# RC_shieldV2.net
KiCad netlist of a schematic drawn in EAGLE
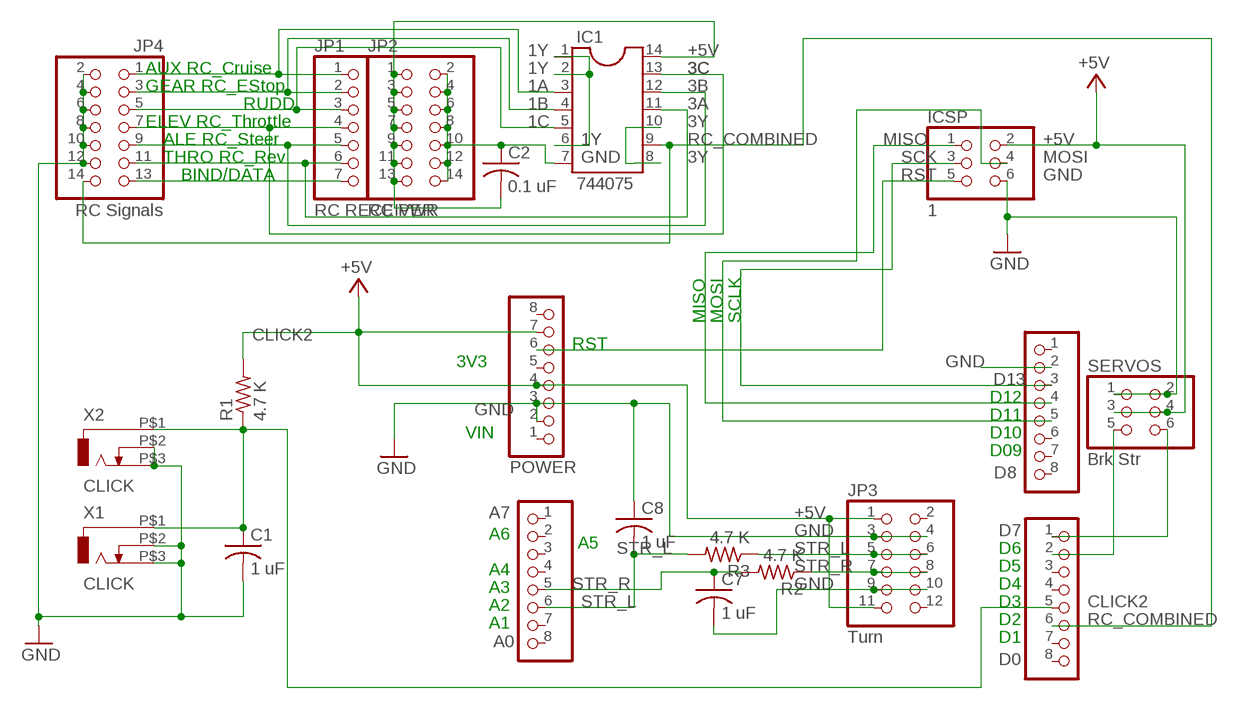
[diagram p0: schematic, sheet 1]

(export (version "E")
  (design (tool "Eeschema 10.0.6"))
  (components
    (comp (ref "A0")
      (value "A7")
      (footprint "eagle-import:1X08")
      (libsource (lib "eagle-import") (part "PINHD-1X8"))
    )
    (comp (ref "C1")
      (value "1 uF")
      (footprint "eagle-import:C025-030X050")
      (libsource (lib "eagle-import") (part "C-US025-030X050"))
    )
    (comp (ref "C2")
      (value "0.1 uF")
      (footprint "eagle-import:C025-030X050")
      (libsource (lib "eagle-import") (part "C-US025-030X050"))
    )
    (comp (ref "C7")
      (value "1 uF")
      (footprint "eagle-import:C025-030X050")
      (libsource (lib "eagle-import") (part "C-US025-030X050"))
    )
    (comp (ref "C8")
      (value "1 uF")
      (footprint "eagle-import:C025-030X050")
      (libsource (lib "eagle-import") (part "C-US025-030X050"))
    )
    (comp (ref "D0")
      (value "D7")
      (footprint "eagle-import:1X08")
      (libsource (lib "eagle-import") (part "PINHD-1X8"))
    )
    (comp (ref "D8")
      (value "D13")
      (footprint "eagle-import:1X08")
      (libsource (lib "eagle-import") (part "PINHD-1X8"))
    )
    (comp (ref "IC1")
      (value "744075")
      (footprint "eagle-import:DIL14")
      (libsource (lib "eagle-import") (part "DIL14"))
    )
    (comp (ref "ICSP")
      (value "1")
      (footprint "eagle-import:2X03")
      (libsource (lib "eagle-import") (part "PINHD-2X3"))
    )
    (comp (ref "JP1")
      (value "RC RECEIVER")
      (footprint "eagle-import:1X07")
      (libsource (lib "eagle-import") (part "PINHD-1X7"))
    )
    (comp (ref "JP2")
      (value "RC PWR")
      (footprint "eagle-import:2X07")
      (libsource (lib "eagle-import") (part "PINHD-2X7"))
    )
    (comp (ref "JP3")
      (value "Turn")
      (footprint "eagle-import:2X06")
      (libsource (lib "eagle-import") (part "PINHD-2X6"))
    )
    (comp (ref "JP4")
      (value "RC Signals")
      (footprint "eagle-import:2X07")
      (libsource (lib "eagle-import") (part "PINHD-2X7"))
    )
    (comp (ref "POWER")
      (value "GND")
      (footprint "eagle-import:1X08")
      (libsource (lib "eagle-import") (part "PINHD-1X8"))
    )
    (comp (ref "R1")
      (value "4.7 K")
      (footprint "eagle-import:0207_10")
      (libsource (lib "eagle-import") (part "R-US_0207/10"))
    )
    (comp (ref "R2")
      (value "4.7 K")
      (footprint "eagle-import:0207_10")
      (libsource (lib "eagle-import") (part "R-US_0207/10"))
    )
    (comp (ref "R3")
      (value "4.7 K")
      (footprint "eagle-import:0207_10")
      (libsource (lib "eagle-import") (part "R-US_0207/10"))
    )
    (comp (ref "SERVOS")
      (value "Brk Str")
      (footprint "eagle-import:2X03")
      (libsource (lib "eagle-import") (part "PINHD-2X3"))
    )
    (comp (ref "X1")
      (value "CLICK")
      (footprint "eagle-import:ODO_JACK")
      (libsource (lib "eagle-import") (part "ODO_JACK"))
    )
    (comp (ref "X2")
      (value "CLICK")
      (footprint "eagle-import:ODO_JACK")
      (libsource (lib "eagle-import") (part "ODO_JACK"))
    )
  )
  (nets
    (net (code "1") (name "+5V") (class "Default")
      (node (ref "C2") (pin "2") (pinfunction "2_2") (pintype "passive"))
      (node (ref "IC1") (pin "14") (pinfunction "14_14") (pintype "passive"))
      (node (ref "ICSP") (pin "2") (pinfunction "2_2") (pintype "passive"))
      (node (ref "JP2") (pin "1") (pinfunction "1_1") (pintype "passive"))
      (node (ref "JP2") (pin "11") (pinfunction "11_11") (pintype "passive"))
      (node (ref "JP2") (pin "13") (pinfunction "13_13") (pintype "passive"))
      (node (ref "JP2") (pin "3") (pinfunction "3_3") (pintype "passive"))
      (node (ref "JP2") (pin "5") (pinfunction "5_5") (pintype "passive"))
      (node (ref "JP2") (pin "7") (pinfunction "7_7") (pintype "passive"))
      (node (ref "JP2") (pin "9") (pinfunction "9_9") (pintype "passive"))
      (node (ref "JP3") (pin "1") (pinfunction "1_1") (pintype "passive"))
      (node (ref "JP3") (pin "11") (pinfunction "11_11") (pintype "passive"))
      (node (ref "POWER") (pin "4") (pinfunction "4_4") (pintype "passive"))
      (node (ref "POWER") (pin "7") (pinfunction "7_7") (pintype "passive"))
      (node (ref "R1") (pin "2") (pinfunction "2_2") (pintype "passive"))
      (node (ref "SERVOS") (pin "3") (pinfunction "3_3") (pintype "passive"))
      (node (ref "SERVOS") (pin "4") (pinfunction "4_4") (pintype "passive"))
    )
    (net (code "2") (name "/1A") (class "Default")
      (node (ref "IC1") (pin "3") (pinfunction "3_3") (pintype "passive"))
      (node (ref "JP1") (pin "1") (pinfunction "1_1") (pintype "passive"))
      (node (ref "JP4") (pin "1") (pinfunction "1_1") (pintype "passive"))
    )
    (net (code "3") (name "/1B") (class "Default")
      (node (ref "IC1") (pin "4") (pinfunction "4_4") (pintype "passive"))
      (node (ref "JP1") (pin "2") (pinfunction "2_2") (pintype "passive"))
      (node (ref "JP4") (pin "3") (pinfunction "3_3") (pintype "passive"))
    )
    (net (code "4") (name "/1C") (class "Default")
      (node (ref "IC1") (pin "5") (pinfunction "5_5") (pintype "passive"))
      (node (ref "JP1") (pin "3") (pinfunction "3_3") (pintype "passive"))
      (node (ref "JP4") (pin "5") (pinfunction "5_5") (pintype "passive"))
    )
    (net (code "5") (name "/1Y") (class "Default")
      (node (ref "IC1") (pin "1") (pinfunction "1_1") (pintype "passive"))
      (node (ref "IC1") (pin "2") (pinfunction "2_2") (pintype "passive"))
      (node (ref "IC1") (pin "6") (pinfunction "6_6") (pintype "passive"))
    )
    (net (code "6") (name "/3A") (class "Default")
      (node (ref "IC1") (pin "11") (pinfunction "11_11") (pintype "passive"))
      (node (ref "JP1") (pin "6") (pinfunction "6_6") (pintype "passive"))
      (node (ref "JP4") (pin "11") (pinfunction "11_11") (pintype "passive"))
    )
    (net (code "7") (name "/3B") (class "Default")
      (node (ref "IC1") (pin "12") (pinfunction "12_12") (pintype "passive"))
      (node (ref "JP1") (pin "5") (pinfunction "5_5") (pintype "passive"))
      (node (ref "JP4") (pin "9") (pinfunction "9_9") (pintype "passive"))
    )
    (net (code "8") (name "/3C") (class "Default")
      (node (ref "IC1") (pin "13") (pinfunction "13_13") (pintype "passive"))
      (node (ref "JP1") (pin "4") (pinfunction "4_4") (pintype "passive"))
      (node (ref "JP4") (pin "7") (pinfunction "7_7") (pintype "passive"))
    )
    (net (code "9") (name "/3Y") (class "Default")
      (node (ref "IC1") (pin "10") (pinfunction "10_10") (pintype "passive"))
      (node (ref "IC1") (pin "8") (pinfunction "8_8") (pintype "passive"))
    )
    (net (code "10") (name "/CLICK2") (class "Default")
      (node (ref "C1") (pin "1") (pinfunction "1_1") (pintype "passive"))
      (node (ref "D0") (pin "5") (pinfunction "5_5") (pintype "passive"))
      (node (ref "R1") (pin "1") (pinfunction "1_1") (pintype "passive"))
      (node (ref "X1") (pin "P$1") (pinfunction "1_P$1") (pintype "passive"))
      (node (ref "X2") (pin "P$1") (pinfunction "1_P$1") (pintype "passive"))
    )
    (net (code "11") (name "/MISO") (class "Default")
      (node (ref "D8") (pin "4") (pinfunction "4_4") (pintype "passive"))
      (node (ref "ICSP") (pin "1") (pinfunction "1_1") (pintype "passive"))
    )
    (net (code "12") (name "/MOSI") (class "Default")
      (node (ref "D8") (pin "5") (pinfunction "5_5") (pintype "passive"))
      (node (ref "ICSP") (pin "4") (pinfunction "4_4") (pintype "passive"))
    )
    (net (code "13") (name "/RC_COMBINED") (class "Default")
      (node (ref "D0") (pin "6") (pinfunction "6_6") (pintype "passive"))
      (node (ref "IC1") (pin "9") (pinfunction "9_9") (pintype "passive"))
      (node (ref "JP4") (pin "14") (pinfunction "14_14") (pintype "passive"))
    )
    (net (code "14") (name "/RST") (class "Default")
      (node (ref "ICSP") (pin "5") (pinfunction "5_5") (pintype "passive"))
      (node (ref "POWER") (pin "6") (pinfunction "6_6") (pintype "passive"))
    )
    (net (code "15") (name "/SCK") (class "Default")
      (node (ref "D8") (pin "3") (pinfunction "3_3") (pintype "passive"))
      (node (ref "ICSP") (pin "3") (pinfunction "3_3") (pintype "passive"))
    )
    (net (code "16") (name "/STR_L") (class "Default")
      (node (ref "A0") (pin "6") (pinfunction "6_6") (pintype "passive"))
      (node (ref "C8") (pin "2") (pinfunction "2_2") (pintype "passive"))
      (node (ref "R3") (pin "2") (pinfunction "2_2") (pintype "passive"))
    )
    (net (code "17") (name "/STR_R") (class "Default")
      (node (ref "A0") (pin "5") (pinfunction "5_5") (pintype "passive"))
      (node (ref "C7") (pin "1") (pinfunction "1_1") (pintype "passive"))
      (node (ref "R2") (pin "2") (pinfunction "2_2") (pintype "passive"))
    )
    (net (code "18") (name "GND") (class "Default")
      (node (ref "C1") (pin "2") (pinfunction "2_2") (pintype "passive"))
      (node (ref "C2") (pin "1") (pinfunction "1_1") (pintype "passive"))
      (node (ref "C7") (pin "2") (pinfunction "2_2") (pintype "passive"))
      (node (ref "C8") (pin "1") (pinfunction "1_1") (pintype "passive"))
      (node (ref "D8") (pin "2") (pinfunction "2_2") (pintype "passive"))
      (node (ref "IC1") (pin "7") (pinfunction "7_7") (pintype "passive"))
      (node (ref "ICSP") (pin "6") (pinfunction "6_6") (pintype "passive"))
      (node (ref "JP2") (pin "10") (pinfunction "10_10") (pintype "passive"))
      (node (ref "JP2") (pin "12") (pinfunction "12_12") (pintype "passive"))
      (node (ref "JP2") (pin "14") (pinfunction "14_14") (pintype "passive"))
      (node (ref "JP2") (pin "2") (pinfunction "2_2") (pintype "passive"))
      (node (ref "JP2") (pin "4") (pinfunction "4_4") (pintype "passive"))
      (node (ref "JP2") (pin "6") (pinfunction "6_6") (pintype "passive"))
      (node (ref "JP2") (pin "8") (pinfunction "8_8") (pintype "passive"))
      (node (ref "JP3") (pin "10") (pinfunction "10_10") (pintype "passive"))
      (node (ref "JP3") (pin "3") (pinfunction "3_3") (pintype "passive"))
      (node (ref "JP3") (pin "4") (pinfunction "4_4") (pintype "passive"))
      (node (ref "JP3") (pin "9") (pinfunction "9_9") (pintype "passive"))
      (node (ref "JP4") (pin "10") (pinfunction "10_10") (pintype "passive"))
      (node (ref "JP4") (pin "12") (pinfunction "12_12") (pintype "passive"))
      (node (ref "JP4") (pin "2") (pinfunction "2_2") (pintype "passive"))
      (node (ref "JP4") (pin "4") (pinfunction "4_4") (pintype "passive"))
      (node (ref "JP4") (pin "6") (pinfunction "6_6") (pintype "passive"))
      (node (ref "JP4") (pin "8") (pinfunction "8_8") (pintype "passive"))
      (node (ref "POWER") (pin "2") (pinfunction "2_2") (pintype "passive"))
      (node (ref "POWER") (pin "3") (pinfunction "3_3") (pintype "passive"))
      (node (ref "SERVOS") (pin "1") (pinfunction "1_1") (pintype "passive"))
      (node (ref "SERVOS") (pin "2") (pinfunction "2_2") (pintype "passive"))
      (node (ref "X1") (pin "P$2") (pinfunction "2_P$2") (pintype "passive"))
      (node (ref "X1") (pin "P$3") (pinfunction "3_P$3") (pintype "passive"))
      (node (ref "X2") (pin "P$2") (pinfunction "2_P$2") (pintype "passive"))
      (node (ref "X2") (pin "P$3") (pinfunction "3_P$3") (pintype "passive"))
    )
    (net (code "19") (name "Net-(D0-Pad1)") (class "Default")
      (node (ref "D0") (pin "1") (pinfunction "1_1") (pintype "passive"))
      (node (ref "SERVOS") (pin "6") (pinfunction "6_6") (pintype "passive"))
    )
    (net (code "20") (name "Net-(D0-Pad2)") (class "Default")
      (node (ref "D0") (pin "2") (pinfunction "2_2") (pintype "passive"))
      (node (ref "SERVOS") (pin "5") (pinfunction "5_5") (pintype "passive"))
    )
    (net (code "21") (name "Net-(JP1-Pad7)") (class "Default")
      (node (ref "JP1") (pin "7") (pinfunction "7_7") (pintype "passive"))
      (node (ref "JP4") (pin "13") (pinfunction "13_13") (pintype "passive"))
    )
    (net (code "22") (name "Net-(JP3-Pad5)") (class "Default")
      (node (ref "JP3") (pin "5") (pinfunction "5_5") (pintype "passive"))
      (node (ref "JP3") (pin "6") (pinfunction "6_6") (pintype "passive"))
      (node (ref "R3") (pin "1") (pinfunction "1_1") (pintype "passive"))
    )
    (net (code "23") (name "Net-(JP3-Pad7)") (class "Default")
      (node (ref "JP3") (pin "7") (pinfunction "7_7") (pintype "passive"))
      (node (ref "JP3") (pin "8") (pinfunction "8_8") (pintype "passive"))
      (node (ref "R2") (pin "1") (pinfunction "1_1") (pintype "passive"))
    )
    (net (code "24") (name "unconnected-(A0-Pad1)") (class "Default")
      (node (ref "A0") (pin "1") (pinfunction "1_1") (pintype "passive"))
    )
    (net (code "25") (name "unconnected-(A0-Pad2)") (class "Default")
      (node (ref "A0") (pin "2") (pinfunction "2_2") (pintype "passive"))
    )
    (net (code "26") (name "unconnected-(A0-Pad3)") (class "Default")
      (node (ref "A0") (pin "3") (pinfunction "3_3") (pintype "passive"))
    )
    (net (code "27") (name "unconnected-(A0-Pad4)") (class "Default")
      (node (ref "A0") (pin "4") (pinfunction "4_4") (pintype "passive"))
    )
    (net (code "28") (name "unconnected-(A0-Pad7)") (class "Default")
      (node (ref "A0") (pin "7") (pinfunction "7_7") (pintype "passive"))
    )
    (net (code "29") (name "unconnected-(A0-Pad8)") (class "Default")
      (node (ref "A0") (pin "8") (pinfunction "8_8") (pintype "passive"))
    )
    (net (code "30") (name "unconnected-(D0-Pad3)") (class "Default")
      (node (ref "D0") (pin "3") (pinfunction "3_3") (pintype "passive"))
    )
    (net (code "31") (name "unconnected-(D0-Pad4)") (class "Default")
      (node (ref "D0") (pin "4") (pinfunction "4_4") (pintype "passive"))
    )
    (net (code "32") (name "unconnected-(D0-Pad7)") (class "Default")
      (node (ref "D0") (pin "7") (pinfunction "7_7") (pintype "passive"))
    )
    (net (code "33") (name "unconnected-(D0-Pad8)") (class "Default")
      (node (ref "D0") (pin "8") (pinfunction "8_8") (pintype "passive"))
    )
    (net (code "34") (name "unconnected-(D8-Pad1)") (class "Default")
      (node (ref "D8") (pin "1") (pinfunction "1_1") (pintype "passive"))
    )
    (net (code "35") (name "unconnected-(D8-Pad6)") (class "Default")
      (node (ref "D8") (pin "6") (pinfunction "6_6") (pintype "passive"))
    )
    (net (code "36") (name "unconnected-(D8-Pad7)") (class "Default")
      (node (ref "D8") (pin "7") (pinfunction "7_7") (pintype "passive"))
    )
    (net (code "37") (name "unconnected-(D8-Pad8)") (class "Default")
      (node (ref "D8") (pin "8") (pinfunction "8_8") (pintype "passive"))
    )
    (net (code "38") (name "unconnected-(JP3-Pad2)") (class "Default")
      (node (ref "JP3") (pin "2") (pinfunction "2_2") (pintype "passive"))
    )
    (net (code "39") (name "unconnected-(JP3-Pad12)") (class "Default")
      (node (ref "JP3") (pin "12") (pinfunction "12_12") (pintype "passive"))
    )
    (net (code "40") (name "unconnected-(POWER-Pad1)") (class "Default")
      (node (ref "POWER") (pin "1") (pinfunction "1_1") (pintype "passive"))
    )
    (net (code "41") (name "unconnected-(POWER-Pad5)") (class "Default")
      (node (ref "POWER") (pin "5") (pinfunction "5_5") (pintype "passive"))
    )
    (net (code "42") (name "unconnected-(POWER-Pad8)") (class "Default")
      (node (ref "POWER") (pin "8") (pinfunction "8_8") (pintype "passive"))
    )
  )
)
